# ProPrj__B__2024-11-06.net
KiCad netlist of a schematic drawn in EasyEDA Pro
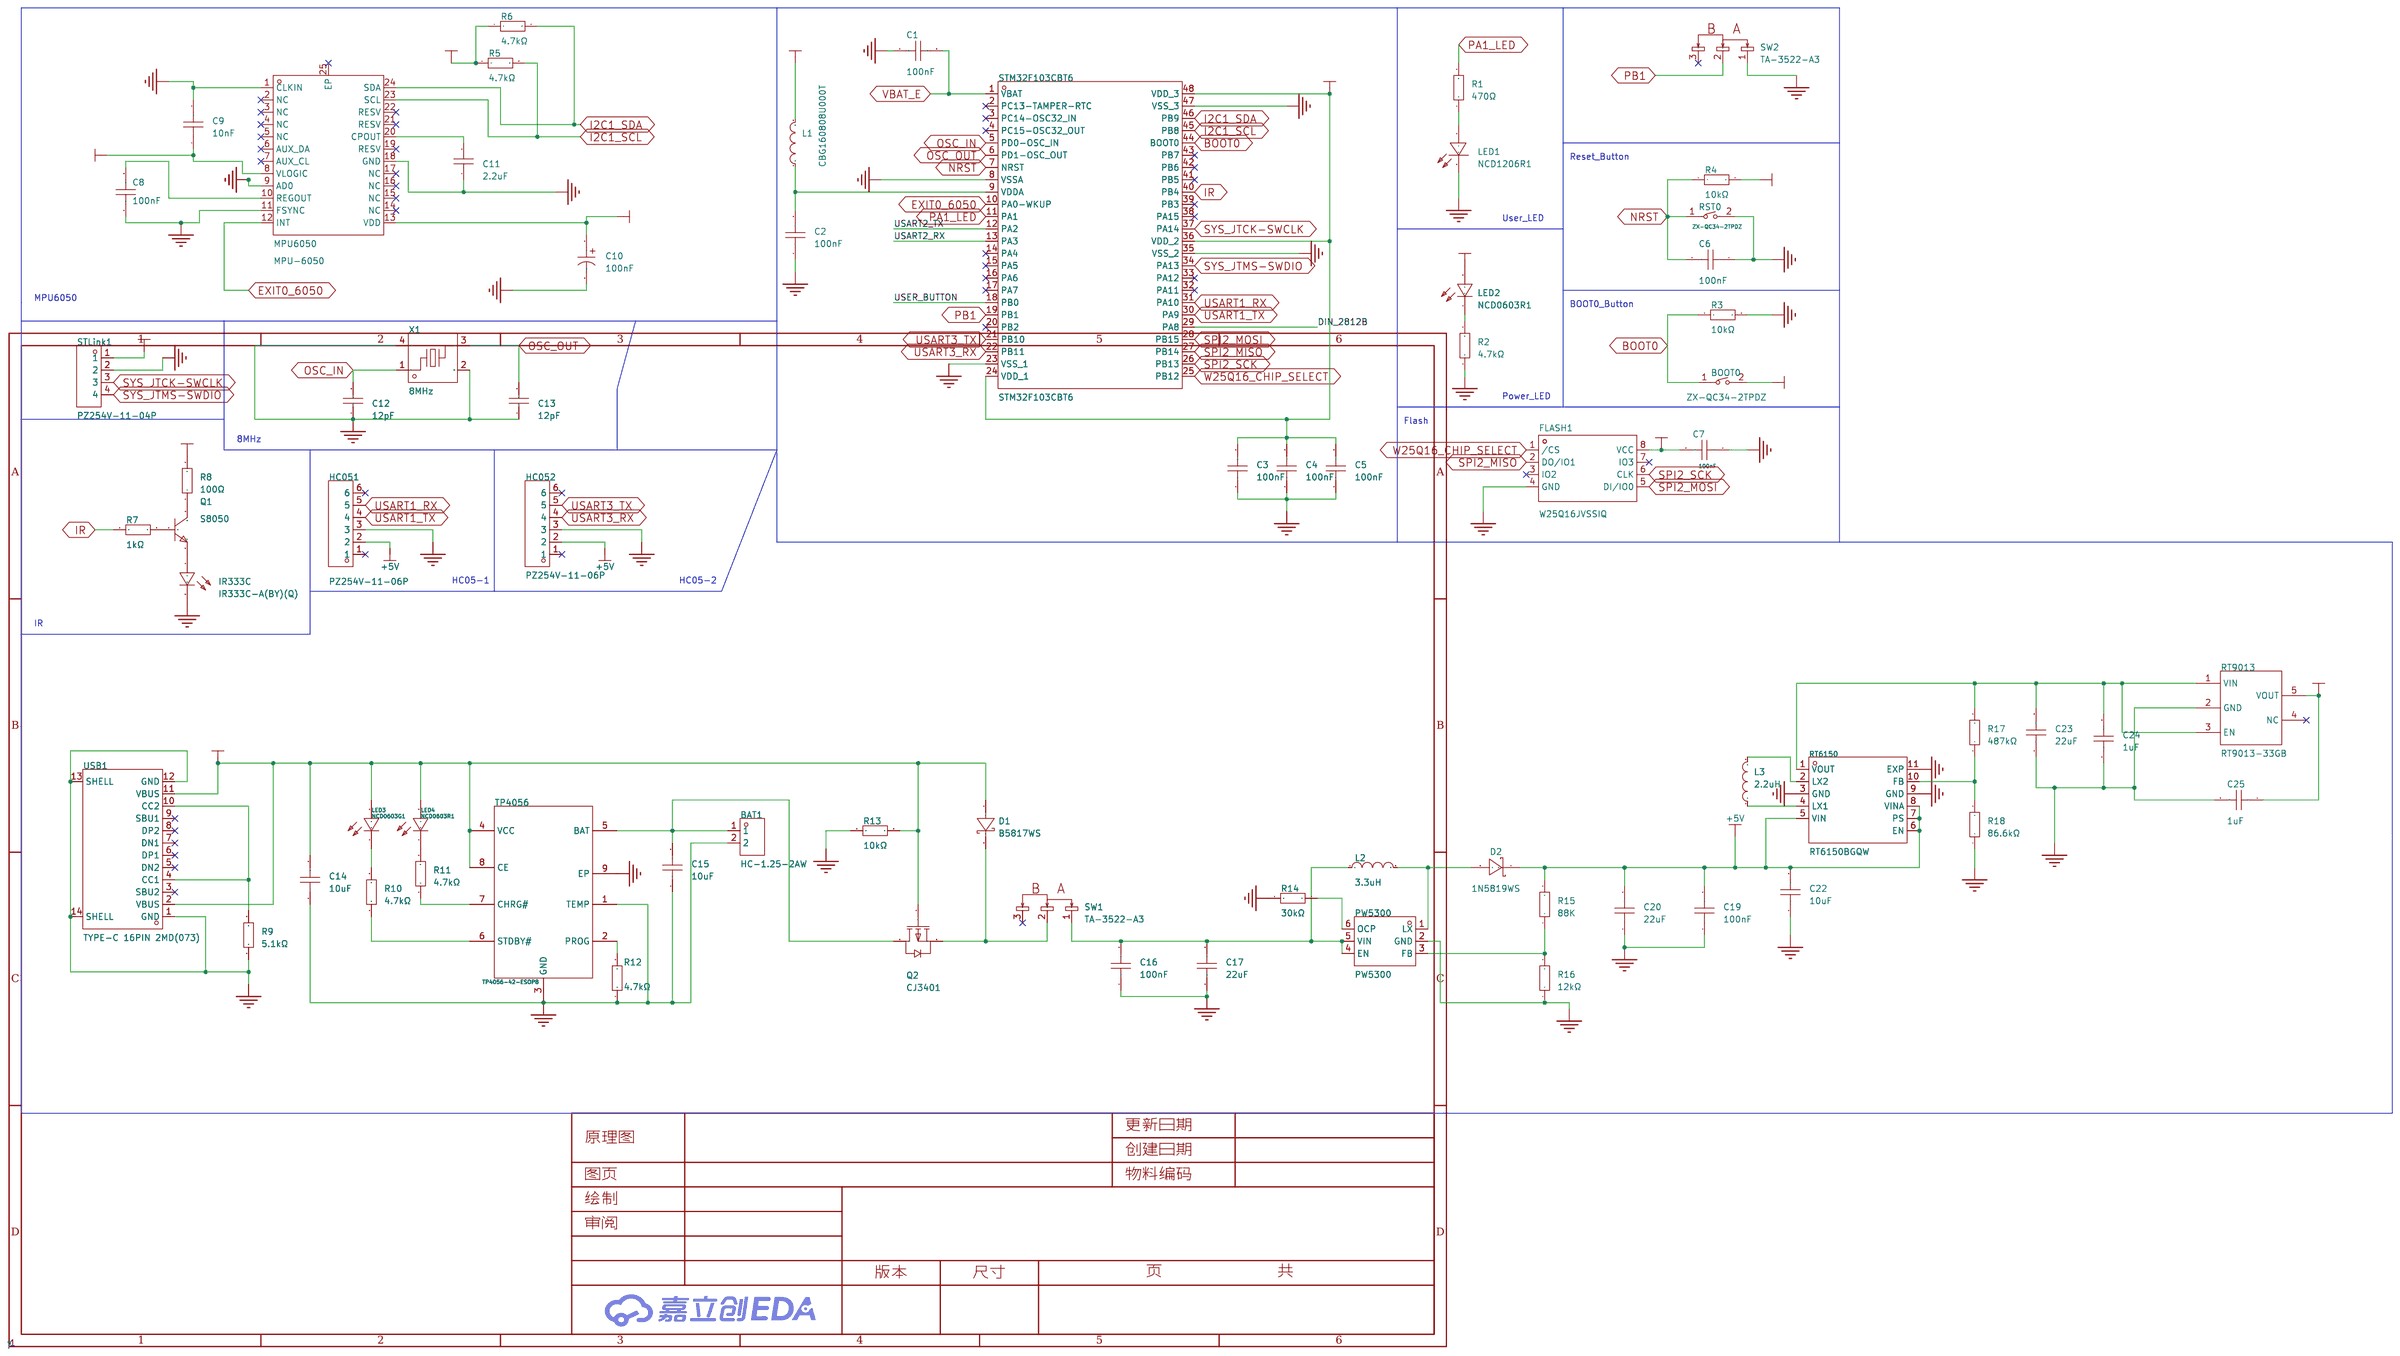
[diagram p0: schematic sheet]

(export (version "E")
  (design (tool "Eeschema 10.0.6"))
  (components
    (comp (ref "BAT1")
      (value "HC-1.25-2AW")
      (footprint "easyedapro:CONN-TH_2P-P1.25_HCTL_HC-1.25-2AW")
      (fields (field (name "Manufacturer") "HCTL(华灿天禄)"))
      (libsource (lib "easyedapro") (part "HC-1.25-2AW"))
    )
    (comp (ref "BOOT0")
      (value "ZX-QC34-2TPDZ")
      (footprint "easyedapro:KEY-SMD_L3.9-W3.0-LS5.0-EH")
      (fields (field (name "Manufacturer") "Megastar(兆星)"))
      (libsource (lib "easyedapro") (part "ZX-QC34-2TPDZ"))
    )
    (comp (ref "C1")
      (value "100nF")
      (footprint "easyedapro:C0603")
      (description "容值:100nF;精度:±10%;额定电压:50V;材质(温度系数):X7R;")
      (fields
        (field (name "Manufacturer Part") "CC0603KRX7R9BB104")
        (field (name "Manufacturer") "YAGEO(国巨)")
      )
      (libsource (lib "easyedapro") (part "CC0603KRX7R9BB104"))
    )
    (comp (ref "C2")
      (value "100nF")
      (footprint "easyedapro:C0603")
      (description "容值:100nF;精度:±10%;额定电压:50V;材质(温度系数):X7R;")
      (fields
        (field (name "Manufacturer Part") "CC0603KRX7R9BB104")
        (field (name "Manufacturer") "YAGEO(国巨)")
      )
      (libsource (lib "easyedapro") (part "CC0603KRX7R9BB104"))
    )
    (comp (ref "C3")
      (value "100nF")
      (footprint "easyedapro:C0603")
      (description "容值:100nF;精度:±10%;额定电压:50V;材质(温度系数):X7R;")
      (fields
        (field (name "Manufacturer Part") "CC0603KRX7R9BB104")
        (field (name "Manufacturer") "YAGEO(国巨)")
      )
      (libsource (lib "easyedapro") (part "CC0603KRX7R9BB104"))
    )
    (comp (ref "C4")
      (value "100nF")
      (footprint "easyedapro:C0603")
      (description "容值:100nF;精度:±10%;额定电压:50V;材质(温度系数):X7R;")
      (fields
        (field (name "Manufacturer Part") "CC0603KRX7R9BB104")
        (field (name "Manufacturer") "YAGEO(国巨)")
      )
      (libsource (lib "easyedapro") (part "CC0603KRX7R9BB104"))
    )
    (comp (ref "C5")
      (value "100nF")
      (footprint "easyedapro:C0603")
      (description "容值:100nF;精度:±10%;额定电压:50V;材质(温度系数):X7R;")
      (fields
        (field (name "Manufacturer Part") "CC0603KRX7R9BB104")
        (field (name "Manufacturer") "YAGEO(国巨)")
      )
      (libsource (lib "easyedapro") (part "CC0603KRX7R9BB104"))
    )
    (comp (ref "C6")
      (value "100nF")
      (footprint "easyedapro:C0603")
      (description "容值:100nF;精度:±10%;额定电压:50V;材质(温度系数):X7R;")
      (fields
        (field (name "Manufacturer Part") "CC0603KRX7R9BB104")
        (field (name "Manufacturer") "YAGEO(国巨)")
      )
      (libsource (lib "easyedapro") (part "CC0603KRX7R9BB104"))
    )
    (comp (ref "C7")
      (value "100nF")
      (footprint "easyedapro:C0603")
      (description "容值:100nF;精度:±10%;额定电压:50V;材质(温度系数):X7R;")
      (fields
        (field (name "Manufacturer Part") "CC0603KRX7R9BB104")
        (field (name "Manufacturer") "YAGEO(国巨)")
      )
      (libsource (lib "easyedapro") (part "CC0603KRX7R9BB104"))
    )
    (comp (ref "C8")
      (value "100nF")
      (footprint "easyedapro:C0603")
      (description "容值:100nF;精度:±10%;额定电压:50V;材质(温度系数):X7R;")
      (fields
        (field (name "Manufacturer Part") "CC0603KRX7R9BB104")
        (field (name "Manufacturer") "YAGEO(国巨)")
      )
      (libsource (lib "easyedapro") (part "CC0603KRX7R9BB104"))
    )
    (comp (ref "C9")
      (value "10nF")
      (footprint "easyedapro:C0603")
      (description "容值:100nF;精度:±10%;额定电压:50V;材质(温度系数):X7R;")
      (fields
        (field (name "Manufacturer Part") "CC0603KRX7R9BB103")
        (field (name "Manufacturer") "YAGEO(国巨)")
      )
      (libsource (lib "easyedapro") (part "CC0603KRX7R9BB104"))
    )
    (comp (ref "C10")
      (value "100nF")
      (footprint "easyedapro:CAP-SMD_L3.2-W1.6-FD")
      (description "容值:100nF;精度:±20%;额定电压:50V;等效串联电阻:20Ω;")
      (fields
        (field (name "Manufacturer Part") "CA45-A-35V-0.1UF-K")
        (field (name "Manufacturer") "CEC(振华新云)")
      )
      (libsource (lib "easyedapro") (part "T491A104M050AT"))
    )
    (comp (ref "C11")
      (value "2.2uF")
      (footprint "easyedapro:C0603")
      (description "容值:2.2uF;精度:±10%;额定电压:16V;材质(温度系数):X5R;")
      (fields
        (field (name "Manufacturer Part") "CL10A225KO8NNNC")
        (field (name "Manufacturer") "SAMSUNG(三星)")
      )
      (libsource (lib "easyedapro") (part "CL10A225KO8NNNC"))
    )
    (comp (ref "C12")
      (value "12pF")
      (footprint "easyedapro:C0603")
      (description "容值:12pF;精度:±5%;额定电压:50V;材质(温度系数):C0G;")
      (fields
        (field (name "Manufacturer Part") "CL10C120JB8NNNC")
        (field (name "Manufacturer") "SAMSUNG(三星)")
      )
      (libsource (lib "easyedapro") (part "CL10C120JB8NNNC"))
    )
    (comp (ref "C13")
      (value "12pF")
      (footprint "easyedapro:C0603")
      (description "容值:12pF;精度:±5%;额定电压:50V;材质(温度系数):C0G;")
      (fields
        (field (name "Manufacturer Part") "CL10C120JB8NNNC")
        (field (name "Manufacturer") "SAMSUNG(三星)")
      )
      (libsource (lib "easyedapro") (part "CL10C120JB8NNNC"))
    )
    (comp (ref "C14")
      (value "10uF")
      (footprint "easyedapro:C0603")
      (description "容值:10uF;精度:±20%;额定电压:16V;材质(温度系数):X5R;")
      (fields
        (field (name "Manufacturer Part") "HGC0603R5106M160NTHJ")
        (field (name "Manufacturer") "Chinocera(华瓷)")
      )
      (libsource (lib "easyedapro") (part "HGC0603R5106M160NTHJ"))
    )
    (comp (ref "C15")
      (value "10uF")
      (footprint "easyedapro:C0603")
      (description "容值:10uF;精度:±20%;额定电压:16V;材质(温度系数):X5R;")
      (fields
        (field (name "Manufacturer Part") "HGC0603R5106M160NTHJ")
        (field (name "Manufacturer") "Chinocera(华瓷)")
      )
      (libsource (lib "easyedapro") (part "HGC0603R5106M160NTHJ"))
    )
    (comp (ref "C16")
      (value "100nF")
      (footprint "easyedapro:C0603")
      (description "容值:100nF;精度:±10%;额定电压:50V;材质(温度系数):X7R;")
      (fields
        (field (name "Manufacturer Part") "CGA0603X7R104K500JT")
        (field (name "Manufacturer") "HRE(芯声)")
      )
      (libsource (lib "easyedapro") (part "cga0603x7r104k500jt"))
    )
    (comp (ref "C17")
      (value "22uF")
      (footprint "easyedapro:C0805")
      (description "容值:22uF;精度:±20%;额定电压:35V;材质(温度系数):X5R;")
      (fields
        (field (name "Manufacturer Part") "CGA0603X5R226M160JT")
        (field (name "Manufacturer") "HRE(芯声)")
      )
      (libsource (lib "easyedapro") (part "CGA0805X5R226M350MT"))
    )
    (comp (ref "C19")
      (value "100nF")
      (footprint "easyedapro:C0603")
      (description "容值:100nF;精度:±10%;额定电压:50V;材质(温度系数):X7R;")
      (fields
        (field (name "Manufacturer Part") "CGA0603X7R104K500JT")
        (field (name "Manufacturer") "HRE(芯声)")
      )
      (libsource (lib "easyedapro") (part "cga0603x7r104k500jt"))
    )
    (comp (ref "C20")
      (value "22uF")
      (footprint "easyedapro:C0805")
      (description "容值:22uF;精度:±20%;额定电压:35V;材质(温度系数):X5R;")
      (fields
        (field (name "Manufacturer Part") "CGA0603X5R226M160JT")
        (field (name "Manufacturer") "HRE(芯声)")
      )
      (libsource (lib "easyedapro") (part "CGA0805X5R226M350MT"))
    )
    (comp (ref "C22")
      (value "10uF")
      (footprint "easyedapro:C0603")
      (description "容值:10uF;精度:±20%;额定电压:16V;材质(温度系数):X5R;")
      (fields
        (field (name "Manufacturer Part") "HGC0603R5106M160NTHJ")
        (field (name "Manufacturer") "Chinocera(华瓷)")
      )
      (libsource (lib "easyedapro") (part "HGC0603R5106M160NTHJ"))
    )
    (comp (ref "C23")
      (value "22uF")
      (footprint "easyedapro:C0603")
      (description "容值:22uF;精度:±20%;额定电压:16V;材质(温度系数):X5R;")
      (fields
        (field (name "Manufacturer Part") "CGA0603X5R226M160JT")
        (field (name "Manufacturer") "HRE(芯声)")
      )
      (libsource (lib "easyedapro") (part "CGA0603X5R226M160JT"))
    )
    (comp (ref "C24")
      (value "1uF")
      (footprint "easyedapro:C0603")
      (description "容值:1uF;精度:±10%;额定电压:16V;材质(温度系数):X5R;")
      (fields
        (field (name "Manufacturer Part") "CGA0603X5R105K160JT")
        (field (name "Manufacturer") "HRE(芯声)")
      )
      (libsource (lib "easyedapro") (part "CGA0603X5R105K160JT"))
    )
    (comp (ref "C25")
      (value "1uF")
      (footprint "easyedapro:C0603")
      (description "容值:1uF;精度:±10%;额定电压:16V;材质(温度系数):X5R;")
      (fields
        (field (name "Manufacturer Part") "CGA0603X5R105K160JT")
        (field (name "Manufacturer") "HRE(芯声)")
      )
      (libsource (lib "easyedapro") (part "CGA0603X5R105K160JT"))
    )
    (comp (ref "D1")
      (value "B5817WS")
      (footprint "easyedapro:SOD-323_L1.7-W1.3-LS2.5-FD")
      (description "二极管配置:独立式;正向压降(Vf):450mV@1.0A;直流反向耐压(Vr):20V;平均整流电流(Io):1A;")
      (fields (field (name "Manufacturer") "宏迦橙"))
      (libsource (lib "easyedapro") (part "B5817WS_C7420329"))
    )
    (comp (ref "D2")
      (value "1N5819WS")
      (footprint "easyedapro:SMB_L4.6-W3.6-LS5.3-RD")
      (description "正向压降(Vf):500mV@3A;直流反向耐压(Vr):40V;平均整流电流(Io):3A;")
      (fields (field (name "Manufacturer") "Hottech(合科泰)"))
      (libsource (lib "easyedapro") (part "SS34_C266556"))
    )
    (comp (ref "FLASH1")
      (value "W25Q16JVSSIQ")
      (footprint "easyedapro:SOIC-8_L5.3-W5.3-P1.27-LS8.0-BL")
      (description "（与C82317为同一颗物料，只是编带方式不一样。）3V 16Mbit Serial Flash Memory with dual/quad SPI")
      (fields (field (name "Manufacturer") "WINBOND(华邦)"))
      (libsource (lib "easyedapro") (part "W25Q16JVSSIQTR"))
    )
    (comp (ref "HC051")
      (value "PZ254V-11-06P")
      (footprint "easyedapro:HDR-TH_6P-P2.54-V-M")
      (fields (field (name "Manufacturer") "XFCN(兴飞)"))
      (libsource (lib "easyedapro") (part "PZ254V-11-06P"))
    )
    (comp (ref "HC052")
      (value "PZ254V-11-06P")
      (footprint "easyedapro:HDR-TH_6P-P2.54-V-M")
      (fields (field (name "Manufacturer") "XFCN(兴飞)"))
      (libsource (lib "easyedapro") (part "PZ254V-11-06P"))
    )
    (comp (ref "IR333C")
      (value "IR333C-A(BY)(Q)")
      (footprint "easyedapro:LED-TH_BD5.0-P2.54-FD")
      (description "波长:940nm;")
      (fields (field (name "Manufacturer") "EVERLIGHT(亿光)"))
      (libsource (lib "easyedapro") (part "ir333c-a(by)(q)"))
    )
    (comp (ref "L1")
      (value "CBG160808U000T")
      (footprint "easyedapro:L0603")
      (description "标称阻抗@测试频率:0Ω@100MHz;直流电阻(RDC):100mΩ;")
      (fields (field (name "Manufacturer") "FH(风华)"))
      (libsource (lib "easyedapro") (part "CBG160808U000T"))
    )
    (comp (ref "L2")
      (value "3.3uH")
      (footprint "easyedapro:IND-SMD_L5.4-W5.2_FXL0530")
      (description "电感值:4.7uH;精度:±20%;额定电流:4.5A;饱和电流(Isat):5A;类型:一体成型电感;")
      (fields (field (name "Manufacturer Part") "VLS252012CX-3R3M-1") (field (name "Manufacturer") "TDK"))
      (libsource (lib "easyedapro") (part "FXL0530-4R7-M"))
    )
    (comp (ref "L3")
      (value "2.2uH")
      (footprint "easyedapro:IND-SMD_L2.5-W2.0_MHCHL2520")
      (description "电感值:2.2uH;精度:±20%;额定电流:3A;饱和电流(Isat):3.8A;类型:一体成型电感;")
      (fields
        (field (name "Manufacturer Part") "FTC252012S2R2MBCA")
        (field (name "Manufacturer") "cjiang(长江微电)")
      )
      (libsource (lib "easyedapro") (part "FTC252012S2R2MBCA"))
    )
    (comp (ref "LED1")
      (value "NCD1206R1")
      (footprint "easyedapro:LED1206-R-RD_RED")
      (fields (field (name "Manufacturer") "国星光电"))
      (libsource (lib "easyedapro") (part "FC-3215HRK-620D"))
    )
    (comp (ref "LED2")
      (value "NCD0603R1")
      (footprint "easyedapro:LED0603-RD_RED")
      (fields (field (name "Manufacturer") "国星光电"))
      (libsource (lib "easyedapro") (part "FC-DA1608HRK-620D"))
    )
    (comp (ref "LED3")
      (value "NCD0603G1")
      (footprint "easyedapro:led0603-rd_1")
      (fields (field (name "Manufacturer") "国星光电"))
      (libsource (lib "easyedapro") (part "FC-D1608UGK-520D10"))
    )
    (comp (ref "LED4")
      (value "NCD0603R1")
      (footprint "easyedapro:led0603-rd_1")
      (fields (field (name "Manufacturer") "国星光电"))
      (libsource (lib "easyedapro") (part "FC-D1608UGK-520D10"))
    )
    (comp (ref "MPU6050")
      (value "MPU-6050")
      (footprint "easyedapro:QFN-24_L4.0-W4.0-P0.50-BL-EP2.7")
      (description "传感器类型:加速度计陀螺仪;")
      (fields (field (name "Manufacturer") "TDK InvenSense(应美盛)"))
      (libsource (lib "easyedapro") (part "MPU-6050_C24112"))
    )
    (comp (ref "PW5300")
      (value "PW5300")
      (footprint "easyedapro:SOT-23-6_L2.9-W1.6-P0.95-LS2.8-BL")
      (libsource (lib "easyedapro") (part "PW5300"))
    )
    (comp (ref "Q1")
      (value "S8050")
      (footprint "easyedapro:SOT-23-3_L2.9-W1.6-P1.90-LS2.8-BR")
      (description "晶体管类型:NPN;集电极电流(Ic):500mA;集射极击穿电压(Vceo):25V;功率(Pd):300mW;")
      (fields (field (name "Manufacturer") "Hottech(合科泰)"))
      (libsource (lib "easyedapro") (part "S8050_C181158"))
    )
    (comp (ref "Q2")
      (value "CJ3401")
      (footprint "easyedapro:SOT-23-3_L2.9-W1.6-P1.90-LS2.8-BR")
      (fields (field (name "Manufacturer") "CJ(江苏长电/长晶)"))
      (libsource (lib "easyedapro") (part "CJ3401"))
    )
    (comp (ref "R1")
      (value "470Ω")
      (footprint "easyedapro:R0603")
      (description "电阻类型:厚膜电阻;阻值:470Ω;精度:±1%;功率:100mW;最大工作电压:75V;温度系数:±100ppm/°C;")
      (fields
        (field (name "Manufacturer Part") "0603WAF4700T5E")
        (field (name "Manufacturer") "UNI-ROYAL(厚声)")
      )
      (libsource (lib "easyedapro") (part "0603WAF4700T5E"))
    )
    (comp (ref "R2")
      (value "4.7kΩ")
      (footprint "easyedapro:R0603")
      (description "电阻类型:厚膜电阻;阻值:4.7kΩ;精度:±1%;功率:100mW;最大工作电压:75V;温度系数:±100ppm/°C;")
      (fields
        (field (name "Manufacturer Part") "0603WAF4701T5E")
        (field (name "Manufacturer") "UNI-ROYAL(厚声)")
      )
      (libsource (lib "easyedapro") (part "0603WAF4701T5E"))
    )
    (comp (ref "R3")
      (value "10kΩ")
      (footprint "easyedapro:R0603")
      (description "电阻类型:厚膜电阻;阻值:10kΩ;精度:±1%;功率:100mW;最大工作电压:75V;温度系数:±100ppm/°C;")
      (fields
        (field (name "Manufacturer Part") "0603WAF1002T5E")
        (field (name "Manufacturer") "UNI-ROYAL(厚声)")
      )
      (libsource (lib "easyedapro") (part "0603WAF1002T5E"))
    )
    (comp (ref "R4")
      (value "10kΩ")
      (footprint "easyedapro:R0603")
      (description "电阻类型:厚膜电阻;阻值:10kΩ;精度:±1%;功率:100mW;最大工作电压:75V;温度系数:±100ppm/°C;")
      (fields
        (field (name "Manufacturer Part") "0603WAF1002T5E")
        (field (name "Manufacturer") "UNI-ROYAL(厚声)")
      )
      (libsource (lib "easyedapro") (part "0603WAF1002T5E"))
    )
    (comp (ref "R5")
      (value "4.7kΩ")
      (footprint "easyedapro:R0603")
      (description "电阻类型:厚膜电阻;阻值:4.7kΩ;精度:±1%;功率:100mW;最大工作电压:75V;温度系数:±100ppm/°C;")
      (fields
        (field (name "Manufacturer Part") "0603WAF4701T5E")
        (field (name "Manufacturer") "UNI-ROYAL(厚声)")
      )
      (libsource (lib "easyedapro") (part "0603WAF4701T5E"))
    )
    (comp (ref "R6")
      (value "4.7kΩ")
      (footprint "easyedapro:R0603")
      (description "电阻类型:厚膜电阻;阻值:4.7kΩ;精度:±1%;功率:100mW;最大工作电压:75V;温度系数:±100ppm/°C;")
      (fields
        (field (name "Manufacturer Part") "0603WAF4701T5E")
        (field (name "Manufacturer") "UNI-ROYAL(厚声)")
      )
      (libsource (lib "easyedapro") (part "0603WAF4701T5E"))
    )
    (comp (ref "R7")
      (value "1kΩ")
      (footprint "easyedapro:R0603")
      (description "电阻类型:厚膜电阻;阻值:1kΩ;精度:±1%;功率:100mW;最大工作电压:75V;温度系数:±100ppm/°C;")
      (fields
        (field (name "Manufacturer Part") "0603WAF1001T5E")
        (field (name "Manufacturer") "UNI-ROYAL(厚声)")
      )
      (libsource (lib "easyedapro") (part "0603WAF1001T5E"))
    )
    (comp (ref "R8")
      (value "100Ω")
      (footprint "easyedapro:R0603")
      (description "电阻类型:厚膜电阻;阻值:100Ω;精度:±1%;功率:100mW;最大工作电压:75V;温度系数:±200ppm/°C;")
      (fields
        (field (name "Manufacturer Part") "0603WAF1000T5E")
        (field (name "Manufacturer") "UNI-ROYAL(厚声)")
      )
      (libsource (lib "easyedapro") (part "0603WAF1000T5E"))
    )
    (comp (ref "R9")
      (value "5.1kΩ")
      (footprint "easyedapro:R0603")
      (description "电阻类型:厚膜电阻;阻值:5.1kΩ;精度:±1%;功率:100mW;最大工作电压:75V;温度系数:±100ppm/°C;")
      (fields
        (field (name "Manufacturer Part") "0603WAF5101T5E")
        (field (name "Manufacturer") "UNI-ROYAL(厚声)")
      )
      (libsource (lib "easyedapro") (part "0603WAF5101T5E"))
    )
    (comp (ref "R10")
      (value "4.7kΩ")
      (footprint "easyedapro:R0603")
      (description "电阻类型:厚膜电阻;阻值:4.7kΩ;精度:±1%;功率:100mW;最大工作电压:75V;温度系数:±100ppm/°C;")
      (fields
        (field (name "Manufacturer Part") "0603WAF4701T5E")
        (field (name "Manufacturer") "UNI-ROYAL(厚声)")
      )
      (libsource (lib "easyedapro") (part "0603WAF4701T5E"))
    )
    (comp (ref "R11")
      (value "4.7kΩ")
      (footprint "easyedapro:R0603")
      (description "电阻类型:厚膜电阻;阻值:4.7kΩ;精度:±1%;功率:100mW;最大工作电压:75V;温度系数:±100ppm/°C;")
      (fields
        (field (name "Manufacturer Part") "0603WAF4701T5E")
        (field (name "Manufacturer") "UNI-ROYAL(厚声)")
      )
      (libsource (lib "easyedapro") (part "0603WAF4701T5E"))
    )
    (comp (ref "R12")
      (value "4.7kΩ")
      (footprint "easyedapro:R0603")
      (description "电阻类型:厚膜电阻;阻值:4.7kΩ;精度:±1%;功率:100mW;最大工作电压:75V;温度系数:±100ppm/°C;")
      (fields
        (field (name "Manufacturer Part") "0603WAF4701T5E")
        (field (name "Manufacturer") "UNI-ROYAL(厚声)")
      )
      (libsource (lib "easyedapro") (part "0603WAF4701T5E"))
    )
    (comp (ref "R13")
      (value "10kΩ")
      (footprint "easyedapro:R0603")
      (description "电阻类型:厚膜电阻;阻值:10kΩ;精度:±1%;功率:100mW;最大工作电压:75V;温度系数:±100ppm/°C;")
      (fields
        (field (name "Manufacturer Part") "0603WAF1002T5E")
        (field (name "Manufacturer") "UNI-ROYAL(厚声)")
      )
      (libsource (lib "easyedapro") (part "0603WAF1002T5E"))
    )
    (comp (ref "R14")
      (value "30kΩ")
      (footprint "easyedapro:R0603")
      (description "电阻类型:厚膜电阻;阻值:30kΩ;精度:±1%;功率:100mW;最大工作电压:75V;温度系数:±100ppm/°C;")
      (fields
        (field (name "Manufacturer Part") "0603WAF3002T5E")
        (field (name "Manufacturer") "UNI-ROYAL(厚声)")
      )
      (libsource (lib "easyedapro") (part "0603WAF3002T5E"))
    )
    (comp (ref "R15")
      (value "88K")
      (footprint "easyedapro:R0603")
      (fields
        (field (name "Manufacturer Part") "RCT0388K7FLF")
        (field (name "Manufacturer") "HKR(香港电阻)")
        (field (name "Tolerance") "±1%")
      )
      (libsource (lib "easyedapro") (part "电阻"))
    )
    (comp (ref "R16")
      (value "12kΩ")
      (footprint "easyedapro:R0603")
      (description "电阻类型:厚膜电阻;阻值:12kΩ;精度:±1%;功率:100mW;最大工作电压:75V;温度系数:±100ppm/°C;")
      (fields
        (field (name "Manufacturer Part") "0603WAF1202T5E")
        (field (name "Manufacturer") "UNI-ROYAL(厚声)")
      )
      (libsource (lib "easyedapro") (part "0603WAF1202T5E"))
    )
    (comp (ref "R17")
      (value "487kΩ")
      (footprint "easyedapro:R0603")
      (description "电阻类型:厚膜电阻;阻值:487kΩ;精度:±1%;功率:100mW;最大工作电压:75V;温度系数:±100ppm/°C;")
      (fields
        (field (name "Manufacturer Part") "0603WAF4873T5E")
        (field (name "Manufacturer") "UNI-ROYAL(厚声)")
      )
      (libsource (lib "easyedapro") (part "0603WAF4873T5E"))
    )
    (comp (ref "R18")
      (value "86.6kΩ")
      (footprint "easyedapro:R0603")
      (description "电阻类型:厚膜电阻;阻值:86.6kΩ;精度:±1%;功率:100mW;最大工作电压:75V;温度系数:±100ppm/°C;")
      (fields
        (field (name "Manufacturer Part") "0603WAF8662T5E")
        (field (name "Manufacturer") "UNI-ROYAL(厚声)")
      )
      (libsource (lib "easyedapro") (part "0603WAF8662T5E"))
    )
    (comp (ref "RST0")
      (value "ZX-QC34-2TPDZ")
      (footprint "easyedapro:KEY-SMD_L3.9-W3.0-LS5.0-EH")
      (fields (field (name "Manufacturer") "Megastar(兆星)"))
      (libsource (lib "easyedapro") (part "ZX-QC34-2TPDZ"))
    )
    (comp (ref "RT6150")
      (value "RT6150BGQW")
      (footprint "easyedapro:WSON-10_L2.5-W2.5-P0.50-BL-EP")
      (description "功能类型:升降压型;输入电压:1.8V~5.5V;输出电压:1.8V~5.5V;输出电流(最大值):800mA;")
      (fields (field (name "Manufacturer") "RICHTEK(立锜)"))
      (libsource (lib "easyedapro") (part "RT6150BGQW"))
    )
    (comp (ref "RT9013")
      (value "RT9013-33GB")
      (footprint "easyedapro:SOT-23-5_L3.0-W1.7-P0.95-LS2.8-BL")
      (description "输出类型:固定;最大输入电压:5.5V;输出电压:3.3V;最大输出电流:500mA;电源纹波抑制比(PSRR):50dB@(10kHz);输出极性:正极;")
      (fields (field (name "Manufacturer") "RICHTEK(立锜)"))
      (libsource (lib "easyedapro") (part "RT9013-33GB"))
    )
    (comp (ref "STLink1")
      (value "PZ254V-11-04P")
      (footprint "easyedapro:HDR-TH_4P-P2.54-V-M")
      (fields (field (name "Manufacturer") "XFCN(兴飞)"))
      (libsource (lib "easyedapro") (part "PZ254V-11-04P_C2691448"))
    )
    (comp (ref "STM32F103CBT6")
      (value "STM32F103CBT6")
      (fields (field (name "Manufacturer") "ST(意法半导体)"))
      (libsource (lib "easyedapro") (part "APM32F103CBT6"))
    )
    (comp (ref "SW1")
      (value "TA-3522-A3")
      (footprint "easyedapro:SW-TH_3P-L9.1-W3.5-P2.50-A3")
      (fields (field (name "Manufacturer") "Yuandi(元迪)"))
      (libsource (lib "easyedapro") (part "TA-3522-A3"))
    )
    (comp (ref "SW2")
      (value "TA-3522-A3")
      (footprint "easyedapro:SW-TH_3P-L9.1-W3.5-P2.50-A3")
      (fields (field (name "Manufacturer") "Yuandi(元迪)"))
      (libsource (lib "easyedapro") (part "TA-3522-A3"))
    )
    (comp (ref "TP4056")
      (value "TP4056-42-ESOP8")
      (footprint "easyedapro:ESOP-8_L4.9-W3.9-P1.27-LS6.0-BL-EP")
      (description "锂电池充电芯片 42代表电池满电电压4.2V。")
      (fields (field (name "Manufacturer") "TOPPOWER(南京拓微)"))
      (libsource (lib "easyedapro") (part "TP4056"))
    )
    (comp (ref "USB1")
      (value "TYPE-C 16PIN 2MD(073)")
      (footprint "easyedapro:USB-C-SMD_TYPE-C-6PIN-2MD-073")
      (description "连接器类型:Type-C;标准:USB 3.1;公母:母;安装方式:卧贴;触点数量:16P;端口数量:1;额定电流 - 电源:5A;工作温度范围:-25°C~+85°C;")
      (fields (field (name "Manufacturer") "SHOU HAN(首韩)"))
      (libsource (lib "easyedapro") (part "TYPE-C 16PIN 2MD(073)"))
    )
    (comp (ref "X1")
      (value "8MHz")
      (footprint "easyedapro:OSC-SMD_4P-L3.2-W2.5-BL")
      (description "晶振类型:贴片晶振;频率:8MHz;常温频差:±10ppm;外接负载电容:12pF;频率稳定度(全温):±20ppm;")
      (fields (field (name "Manufacturer Part") "X32258MOB4SI") (field (name "Manufacturer") "YXC(扬兴晶振)"))
      (libsource (lib "easyedapro") (part "x32258mob4si"))
    )
  )
  (nets
    (net (code "1") (name "+5V") (class "Default")
      (node (ref "C19") (pin "2") (pinfunction "2_2") (pintype "unspecified"))
      (node (ref "C20") (pin "2") (pinfunction "2_2") (pintype "unspecified"))
      (node (ref "C22") (pin "2") (pinfunction "2_2") (pintype "unspecified"))
      (node (ref "D2") (pin "1") (pinfunction "C_1") (pintype "unspecified"))
      (node (ref "HC051") (pin "2") (pinfunction "2_2") (pintype "unspecified"))
      (node (ref "HC052") (pin "2") (pinfunction "2_2") (pintype "unspecified"))
      (node (ref "R15") (pin "2") (pinfunction "2_2") (pintype "input"))
      (node (ref "RT6150") (pin "5") (pinfunction "VIN_5") (pintype "input"))
      (node (ref "RT6150") (pin "6") (pinfunction "EN_6") (pintype "input"))
      (node (ref "RT6150") (pin "7") (pinfunction "PS_7") (pintype "input"))
      (node (ref "RT6150") (pin "8") (pinfunction "VINA_8") (pintype "input"))
    )
    (net (code "2") (name "/DIN_2812B") (class "Default")
      (node (ref "STM32F103CBT6") (pin "29") (pinfunction "PA8_29") (pintype "unspecified"))
    )
    (net (code "3") (name "/USART2_RX") (class "Default")
      (node (ref "STM32F103CBT6") (pin "13") (pinfunction "PA3_13") (pintype "unspecified"))
    )
    (net (code "4") (name "/USART2_TX") (class "Default")
      (node (ref "STM32F103CBT6") (pin "12") (pinfunction "PA2_12") (pintype "unspecified"))
    )
    (net (code "5") (name "/USER_BUTTON") (class "Default")
      (node (ref "STM32F103CBT6") (pin "18") (pinfunction "PB0_18") (pintype "unspecified"))
    )
    (net (code "6") (name "3V3") (class "Default")
      (node (ref "BOOT0") (pin "2") (pinfunction "2_2") (pintype "unspecified"))
      (node (ref "C10") (pin "1") (pinfunction "1_1") (pintype "input"))
      (node (ref "C25") (pin "1") (pinfunction "1_1") (pintype "unspecified"))
      (node (ref "C3") (pin "2") (pinfunction "2_2") (pintype "unspecified"))
      (node (ref "C4") (pin "2") (pinfunction "2_2") (pintype "unspecified"))
      (node (ref "C5") (pin "2") (pinfunction "2_2") (pintype "unspecified"))
      (node (ref "C7") (pin "2") (pinfunction "2_2") (pintype "unspecified"))
      (node (ref "C9") (pin "1") (pinfunction "1_1") (pintype "unspecified"))
      (node (ref "FLASH1") (pin "8") (pinfunction "VCC_8") (pintype "unspecified"))
      (node (ref "L1") (pin "2") (pinfunction "2_2") (pintype "unspecified"))
      (node (ref "LED2") (pin "2") (pinfunction "A_2") (pintype "input"))
      (node (ref "MPU6050") (pin "13") (pinfunction "VDD_13") (pintype "unspecified"))
      (node (ref "MPU6050") (pin "8") (pinfunction "VLOGIC_8") (pintype "unspecified"))
      (node (ref "R4") (pin "2") (pinfunction "2_2") (pintype "input"))
      (node (ref "R5") (pin "1") (pinfunction "1_1") (pintype "input"))
      (node (ref "R6") (pin "1") (pinfunction "1_1") (pintype "input"))
      (node (ref "R8") (pin "2") (pinfunction "2_2") (pintype "input"))
      (node (ref "RT9013") (pin "5") (pinfunction "VOUT_5") (pintype "unspecified"))
      (node (ref "STLink1") (pin "1") (pinfunction "1_1") (pintype "unspecified"))
      (node (ref "STM32F103CBT6") (pin "24") (pinfunction "VDD_1_24") (pintype "unspecified"))
      (node (ref "STM32F103CBT6") (pin "36") (pinfunction "VDD_2_36") (pintype "unspecified"))
      (node (ref "STM32F103CBT6") (pin "48") (pinfunction "VDD_3_48") (pintype "unspecified"))
    )
    (net (code "7") (name "BOOT0") (class "Default")
      (node (ref "BOOT0") (pin "1") (pinfunction "1_1") (pintype "unspecified"))
      (node (ref "R3") (pin "1") (pinfunction "1_1") (pintype "input"))
      (node (ref "STM32F103CBT6") (pin "44") (pinfunction "BOOT0_44") (pintype "unspecified"))
    )
    (net (code "8") (name "EXIT0_6050") (class "Default")
      (node (ref "MPU6050") (pin "12") (pinfunction "INT_12") (pintype "unspecified"))
      (node (ref "STM32F103CBT6") (pin "10") (pinfunction "PA0-WKUP_10") (pintype "unspecified"))
    )
    (net (code "9") (name "GND") (class "Default")
      (node (ref "BAT1") (pin "2") (pinfunction "2_2") (pintype "unspecified"))
      (node (ref "C1") (pin "1") (pinfunction "1_1") (pintype "unspecified"))
      (node (ref "C10") (pin "2") (pinfunction "2_2") (pintype "input"))
      (node (ref "C11") (pin "1") (pinfunction "1_1") (pintype "input"))
      (node (ref "C12") (pin "1") (pinfunction "1_1") (pintype "input"))
      (node (ref "C13") (pin "1") (pinfunction "1_1") (pintype "input"))
      (node (ref "C14") (pin "1") (pinfunction "1_1") (pintype "unspecified"))
      (node (ref "C15") (pin "1") (pinfunction "1_1") (pintype "unspecified"))
      (node (ref "C16") (pin "1") (pinfunction "1_1") (pintype "unspecified"))
      (node (ref "C17") (pin "1") (pinfunction "1_1") (pintype "unspecified"))
      (node (ref "C19") (pin "1") (pinfunction "1_1") (pintype "unspecified"))
      (node (ref "C2") (pin "1") (pinfunction "1_1") (pintype "unspecified"))
      (node (ref "C20") (pin "1") (pinfunction "1_1") (pintype "unspecified"))
      (node (ref "C22") (pin "1") (pinfunction "1_1") (pintype "unspecified"))
      (node (ref "C23") (pin "1") (pinfunction "1_1") (pintype "unspecified"))
      (node (ref "C24") (pin "1") (pinfunction "1_1") (pintype "unspecified"))
      (node (ref "C25") (pin "2") (pinfunction "2_2") (pintype "unspecified"))
      (node (ref "C3") (pin "1") (pinfunction "1_1") (pintype "unspecified"))
      (node (ref "C4") (pin "1") (pinfunction "1_1") (pintype "unspecified"))
      (node (ref "C5") (pin "1") (pinfunction "1_1") (pintype "unspecified"))
      (node (ref "C6") (pin "1") (pinfunction "1_1") (pintype "unspecified"))
      (node (ref "C7") (pin "1") (pinfunction "1_1") (pintype "unspecified"))
      (node (ref "C8") (pin "1") (pinfunction "1_1") (pintype "unspecified"))
      (node (ref "C9") (pin "2") (pinfunction "2_2") (pintype "unspecified"))
      (node (ref "FLASH1") (pin "4") (pinfunction "GND_4") (pintype "unspecified"))
      (node (ref "HC051") (pin "3") (pinfunction "3_3") (pintype "unspecified"))
      (node (ref "HC052") (pin "3") (pinfunction "3_3") (pintype "unspecified"))
      (node (ref "IR333C") (pin "2") (pinfunction "C_2") (pintype "input"))
      (node (ref "LED1") (pin "2") (pinfunction "K_2") (pintype "unspecified"))
      (node (ref "MPU6050") (pin "1") (pinfunction "CLKIN_1") (pintype "unspecified"))
      (node (ref "MPU6050") (pin "11") (pinfunction "FSYNC_11") (pintype "unspecified"))
      (node (ref "MPU6050") (pin "18") (pinfunction "GND_18") (pintype "unspecified"))
      (node (ref "MPU6050") (pin "9") (pinfunction "AD0_9") (pintype "unspecified"))
      (node (ref "PW5300") (pin "2") (pinfunction "GND_2") (pintype "unspecified"))
      (node (ref "R12") (pin "1") (pinfunction "1_1") (pintype "input"))
      (node (ref "R13") (pin "1") (pinfunction "1_1") (pintype "input"))
      (node (ref "R14") (pin "1") (pinfunction "1_1") (pintype "input"))
      (node (ref "R16") (pin "1") (pinfunction "1_1") (pintype "input"))
      (node (ref "R18") (pin "1") (pinfunction "1_1") (pintype "input"))
      (node (ref "R2") (pin "1") (pinfunction "1_1") (pintype "input"))
      (node (ref "R3") (pin "2") (pinfunction "2_2") (pintype "input"))
      (node (ref "R9") (pin "1") (pinfunction "1_1") (pintype "input"))
      (node (ref "RST0") (pin "2") (pinfunction "2_2") (pintype "unspecified"))
      (node (ref "RT6150") (pin "11") (pinfunction "EXP_11") (pintype "input"))
      (node (ref "RT6150") (pin "3") (pinfunction "GND_3") (pintype "input"))
      (node (ref "RT6150") (pin "9") (pinfunction "GND_9") (pintype "input"))
      (node (ref "RT9013") (pin "2") (pinfunction "GND_2") (pintype "unspecified"))
      (node (ref "STLink1") (pin "2") (pinfunction "2_2") (pintype "unspecified"))
      (node (ref "STM32F103CBT6") (pin "23") (pinfunction "VSS_1_23") (pintype "unspecified"))
      (node (ref "STM32F103CBT6") (pin "35") (pinfunction "VSS_2_35") (pintype "unspecified"))
      (node (ref "STM32F103CBT6") (pin "47") (pinfunction "VSS_3_47") (pintype "unspecified"))
      (node (ref "STM32F103CBT6") (pin "8") (pinfunction "VSSA_8") (pintype "unspecified"))
      (node (ref "SW2") (pin "1") (pinfunction "1_1") (pintype "unspecified"))
      (node (ref "TP4056") (pin "1") (pinfunction "TEMP_1") (pintype "unspecified"))
      (node (ref "TP4056") (pin "3") (pinfunction "GND_3") (pintype "unspecified"))
      (node (ref "TP4056") (pin "9") (pinfunction "EP_9") (pintype "unspecified"))
      (node (ref "USB1") (pin "1") (pinfunction "GND_1") (pintype "unspecified"))
      (node (ref "USB1") (pin "12") (pinfunction "GND_12") (pintype "unspecified"))
      (node (ref "USB1") (pin "13") (pinfunction "SHELL_13") (pintype "unspecified"))
      (node (ref "USB1") (pin "14") (pinfunction "SHELL_14") (pintype "unspecified"))
      (node (ref "X1") (pin "2") (pinfunction "GND_2") (pintype "input"))
      (node (ref "X1") (pin "4") (pinfunction "GND_4") (pintype "input"))
    )
    (net (code "10") (name "I2C1_SCL") (class "Default")
      (node (ref "MPU6050") (pin "23") (pinfunction "SCL_23") (pintype "unspecified"))
      (node (ref "R5") (pin "2") (pinfunction "2_2") (pintype "input"))
      (node (ref "STM32F103CBT6") (pin "45") (pinfunction "PB8_45") (pintype "unspecified"))
    )
    (net (code "11") (name "I2C1_SDA") (class "Default")
      (node (ref "MPU6050") (pin "24") (pinfunction "SDA_24") (pintype "unspecified"))
      (node (ref "R6") (pin "2") (pinfunction "2_2") (pintype "input"))
      (node (ref "STM32F103CBT6") (pin "46") (pinfunction "PB9_46") (pintype "unspecified"))
    )
    (net (code "12") (name "IR") (class "Default")
      (node (ref "R7") (pin "1") (pinfunction "1_1") (pintype "input"))
      (node (ref "STM32F103CBT6") (pin "40") (pinfunction "PB4_40") (pintype "unspecified"))
    )
    (net (code "13") (name "NRST") (class "Default")
      (node (ref "C6") (pin "2") (pinfunction "2_2") (pintype "unspecified"))
      (node (ref "R4") (pin "1") (pinfunction "1_1") (pintype "input"))
      (node (ref "RST0") (pin "1") (pinfunction "1_1") (pintype "unspecified"))
      (node (ref "STM32F103CBT6") (pin "7") (pinfunction "NRST_7") (pintype "unspecified"))
    )
    (net (code "14") (name "Net-(D1-K)") (class "Default")
      (node (ref "D1") (pin "2") (pinfunction "K_2") (pintype "unspecified"))
      (node (ref "Q2") (pin "2") (pinfunction "S_2") (pintype "unspecified"))
      (node (ref "SW1") (pin "2") (pinfunction "2_2") (pintype "unspecified"))
    )
    (net (code "15") (name "Net-(D2-A)") (class "Default")
      (node (ref "D2") (pin "2") (pinfunction "A_2") (pintype "unspecified"))
      (node (ref "L2") (pin "2") (pinfunction "2_2") (pintype "unspecified"))
      (node (ref "PW5300") (pin "1") (pinfunction "LX_1") (pintype "unspecified"))
    )
    (net (code "16") (name "Net-(IR333C-A)") (class "Default")
      (node (ref "IR333C") (pin "1") (pinfunction "A_1") (pintype "input"))
      (node (ref "Q1") (pin "2") (pinfunction "2_2") (pintype "input"))
    )
    (net (code "17") (name "Net-(LED1-A)") (class "Default")
      (node (ref "LED1") (pin "1") (pinfunction "A_1") (pintype "unspecified"))
      (node (ref "R1") (pin "1") (pinfunction "1_1") (pintype "input"))
    )
    (net (code "18") (name "Net-(LED2-K)") (class "Default")
      (node (ref "LED2") (pin "1") (pinfunction "K_1") (pintype "input"))
      (node (ref "R2") (pin "2") (pinfunction "2_2") (pintype "input"))
    )
    (net (code "19") (name "Net-(LED3-K)") (class "Default")
      (node (ref "LED3") (pin "1") (pinfunction "K_1") (pintype "input"))
      (node (ref "R10") (pin "2") (pinfunction "2_2") (pintype "input"))
    )
    (net (code "20") (name "Net-(LED4-K)") (class "Default")
      (node (ref "LED4") (pin "1") (pinfunction "K_1") (pintype "input"))
      (node (ref "R11") (pin "2") (pinfunction "2_2") (pintype "input"))
    )
    (net (code "21") (name "Net-(MPU6050-CPOUT)") (class "Default")
      (node (ref "C11") (pin "2") (pinfunction "2_2") (pintype "input"))
      (node (ref "MPU6050") (pin "20") (pinfunction "CPOUT_20") (pintype "unspecified"))
    )
    (net (code "22") (name "Net-(MPU6050-REGOUT)") (class "Default")
      (node (ref "C8") (pin "2") (pinfunction "2_2") (pintype "unspecified"))
      (node (ref "MPU6050") (pin "10") (pinfunction "REGOUT_10") (pintype "unspecified"))
    )
    (net (code "23") (name "Net-(PW5300-EN)") (class "Default")
      (node (ref "C16") (pin "2") (pinfunction "2_2") (pintype "unspecified"))
      (node (ref "C17") (pin "2") (pinfunction "2_2") (pintype "unspecified"))
      (node (ref "L2") (pin "1") (pinfunction "1_1") (pintype "unspecified"))
      (node (ref "PW5300") (pin "4") (pinfunction "EN_4") (pintype "unspecified"))
      (node (ref "PW5300") (pin "5") (pinfunction "VIN_5") (pintype "unspecified"))
      (node (ref "SW1") (pin "1") (pinfunction "1_1") (pintype "unspecified"))
    )
    (net (code "24") (name "Net-(PW5300-FB)") (class "Default")
      (node (ref "PW5300") (pin "3") (pinfunction "FB_3") (pintype "unspecified"))
      (node (ref "R15") (pin "1") (pinfunction "1_1") (pintype "input"))
      (node (ref "R16") (pin "2") (pinfunction "2_2") (pintype "input"))
    )
    (net (code "25") (name "Net-(PW5300-OCP)") (class "Default")
      (node (ref "PW5300") (pin "6") (pinfunction "OCP_6") (pintype "unspecified"))
      (node (ref "R14") (pin "2") (pinfunction "2_2") (pintype "input"))
    )
    (net (code "26") (name "Net-(Q1-Pad1)") (class "Default")
      (node (ref "Q1") (pin "1") (pinfunction "1_1") (pintype "input"))
      (node (ref "R7") (pin "2") (pinfunction "2_2") (pintype "input"))
    )
    (net (code "27") (name "Net-(Q1-Pad3)") (class "Default")
      (node (ref "Q1") (pin "3") (pinfunction "3_3") (pintype "input"))
      (node (ref "R8") (pin "1") (pinfunction "1_1") (pintype "input"))
    )
    (net (code "28") (name "Net-(Q2-D)") (class "Default")
      (node (ref "BAT1") (pin "1") (pinfunction "1_1") (pintype "unspecified"))
      (node (ref "C15") (pin "2") (pinfunction "2_2") (pintype "unspecified"))
      (node (ref "Q2") (pin "3") (pinfunction "D_3") (pintype "unspecified"))
      (node (ref "TP4056") (pin "5") (pinfunction "BAT_5") (pintype "unspecified"))
    )
    (net (code "29") (name "Net-(RT6150-FB)") (class "Default")
      (node (ref "R17") (pin "1") (pinfunction "1_1") (pintype "input"))
      (node (ref "R18") (pin "2") (pinfunction "2_2") (pintype "input"))
      (node (ref "RT6150") (pin "10") (pinfunction "FB_10") (pintype "input"))
    )
    (net (code "30") (name "Net-(RT6150-LX1)") (class "Default")
      (node (ref "L3") (pin "1") (pinfunction "1_1") (pintype "unspecified"))
      (node (ref "RT6150") (pin "4") (pinfunction "LX1_4") (pintype "input"))
    )
    (net (code "31") (name "Net-(RT6150-LX2)") (class "Default")
      (node (ref "L3") (pin "2") (pinfunction "2_2") (pintype "unspecified"))
      (node (ref "RT6150") (pin "2") (pinfunction "LX2_2") (pintype "input"))
    )
    (net (code "32") (name "Net-(RT6150-VOUT)") (class "Default")
      (node (ref "C23") (pin "2") (pinfunction "2_2") (pintype "unspecified"))
      (node (ref "C24") (pin "2") (pinfunction "2_2") (pintype "unspecified"))
      (node (ref "R17") (pin "2") (pinfunction "2_2") (pintype "input"))
      (node (ref "RT6150") (pin "1") (pinfunction "VOUT_1") (pintype "input"))
      (node (ref "RT9013") (pin "1") (pinfunction "VIN_1") (pintype "unspecified"))
      (node (ref "RT9013") (pin "3") (pinfunction "EN_3") (pintype "unspecified"))
    )
    (net (code "33") (name "Net-(STM32F103CBT6-VDDA)") (class "Default")
      (node (ref "C2") (pin "2") (pinfunction "2_2") (pintype "unspecified"))
      (node (ref "L1") (pin "1") (pinfunction "1_1") (pintype "unspecified"))
      (node (ref "STM32F103CBT6") (pin "9") (pinfunction "VDDA_9") (pintype "unspecified"))
    )
    (net (code "34") (name "Net-(TP4056-CHRG#)") (class "Default")
      (node (ref "R11") (pin "1") (pinfunction "1_1") (pintype "input"))
      (node (ref "TP4056") (pin "7") (pinfunction "CHRG#_7") (pintype "unspecified"))
    )
    (net (code "35") (name "Net-(TP4056-PROG)") (class "Default")
      (node (ref "R12") (pin "2") (pinfunction "2_2") (pintype "input"))
      (node (ref "TP4056") (pin "2") (pinfunction "PROG_2") (pintype "unspecified"))
    )
    (net (code "36") (name "Net-(TP4056-STDBY#)") (class "Default")
      (node (ref "R10") (pin "1") (pinfunction "1_1") (pintype "input"))
      (node (ref "TP4056") (pin "6") (pinfunction "STDBY#_6") (pintype "unspecified"))
    )
    (net (code "37") (name "Net-(USB1-CC1)") (class "Default")
      (node (ref "R9") (pin "2") (pinfunction "2_2") (pintype "input"))
      (node (ref "USB1") (pin "10") (pinfunction "CC2_10") (pintype "unspecified"))
      (node (ref "USB1") (pin "4") (pinfunction "CC1_4") (pintype "unspecified"))
    )
    (net (code "38") (name "OSC_IN") (class "Default")
      (node (ref "C12") (pin "2") (pinfunction "2_2") (pintype "input"))
      (node (ref "STM32F103CBT6") (pin "5") (pinfunction "PD0-OSC_IN_5") (pintype "unspecified"))
      (node (ref "X1") (pin "1") (pinfunction "1_1") (pintype "input"))
    )
    (net (code "39") (name "OSC_OUT") (class "Default")
      (node (ref "C13") (pin "2") (pinfunction "2_2") (pintype "input"))
      (node (ref "STM32F103CBT6") (pin "6") (pinfunction "PD1-OSC_OUT_6") (pintype "unspecified"))
      (node (ref "X1") (pin "3") (pinfunction "3_3") (pintype "input"))
    )
    (net (code "40") (name "PA1_LED") (class "Default")
      (node (ref "R1") (pin "2") (pinfunction "2_2") (pintype "input"))
      (node (ref "STM32F103CBT6") (pin "11") (pinfunction "PA1_11") (pintype "unspecified"))
    )
    (net (code "41") (name "PB1") (class "Default")
      (node (ref "STM32F103CBT6") (pin "19") (pinfunction "PB1_19") (pintype "unspecified"))
      (node (ref "SW2") (pin "2") (pinfunction "2_2") (pintype "unspecified"))
    )
    (net (code "42") (name "SPI2_MISO") (class "Default")
      (node (ref "FLASH1") (pin "2") (pinfunction "DO/IO1_2") (pintype "unspecified"))
      (node (ref "STM32F103CBT6") (pin "27") (pinfunction "PB14_27") (pintype "unspecified"))
    )
    (net (code "43") (name "SPI2_MOSI") (class "Default")
      (node (ref "FLASH1") (pin "5") (pinfunction "DI/IO0_5") (pintype "unspecified"))
      (node (ref "STM32F103CBT6") (pin "28") (pinfunction "PB15_28") (pintype "unspecified"))
    )
    (net (code "44") (name "SPI2_SCK") (class "Default")
      (node (ref "FLASH1") (pin "6") (pinfunction "CLK_6") (pintype "unspecified"))
      (node (ref "STM32F103CBT6") (pin "26") (pinfunction "PB13_26") (pintype "unspecified"))
    )
    (net (code "45") (name "SYS_JTCK-SWCLK") (class "Default")
      (node (ref "STLink1") (pin "3") (pinfunction "3_3") (pintype "unspecified"))
      (node (ref "STM32F103CBT6") (pin "37") (pinfunction "PA14_37") (pintype "unspecified"))
    )
    (net (code "46") (name "SYS_JTMS-SWDIO") (class "Default")
      (node (ref "STLink1") (pin "4") (pinfunction "4_4") (pintype "unspecified"))
      (node (ref "STM32F103CBT6") (pin "34") (pinfunction "PA13_34") (pintype "unspecified"))
    )
    (net (code "47") (name "USART1_RX") (class "Default")
      (node (ref "HC051") (pin "5") (pinfunction "5_5") (pintype "unspecified"))
      (node (ref "STM32F103CBT6") (pin "31") (pinfunction "PA10_31") (pintype "unspecified"))
    )
    (net (code "48") (name "USART1_TX") (class "Default")
      (node (ref "HC051") (pin "4") (pinfunction "4_4") (pintype "unspecified"))
      (node (ref "STM32F103CBT6") (pin "30") (pinfunction "PA9_30") (pintype "unspecified"))
    )
    (net (code "49") (name "USART3_RX") (class "Default")
      (node (ref "HC052") (pin "4") (pinfunction "4_4") (pintype "unspecified"))
      (node (ref "STM32F103CBT6") (pin "22") (pinfunction "PB11_22") (pintype "unspecified"))
    )
    (net (code "50") (name "USART3_TX") (class "Default")
      (node (ref "HC052") (pin "5") (pinfunction "5_5") (pintype "unspecified"))
      (node (ref "STM32F103CBT6") (pin "21") (pinfunction "PB10_21") (pintype "unspecified"))
    )
    (net (code "51") (name "VBAT_E") (class "Default")
      (node (ref "C1") (pin "2") (pinfunction "2_2") (pintype "unspecified"))
      (node (ref "STM32F103CBT6") (pin "1") (pinfunction "VBAT_1") (pintype "unspecified"))
    )
    (net (code "52") (name "VCC_USB") (class "Default")
      (node (ref "C14") (pin "2") (pinfunction "2_2") (pintype "unspecified"))
      (node (ref "D1") (pin "1") (pinfunction "A_1") (pintype "unspecified"))
      (node (ref "LED3") (pin "2") (pinfunction "A_2") (pintype "input"))
      (node (ref "LED4") (pin "2") (pinfunction "A_2") (pintype "input"))
      (node (ref "Q2") (pin "1") (pinfunction "G_1") (pintype "unspecified"))
      (node (ref "R13") (pin "2") (pinfunction "2_2") (pintype "input"))
      (node (ref "TP4056") (pin "4") (pinfunction "VCC_4") (pintype "unspecified"))
      (node (ref "TP4056") (pin "8") (pinfunction "CE_8") (pintype "unspecified"))
      (node (ref "USB1") (pin "11") (pinfunction "VBUS_11") (pintype "unspecified"))
      (node (ref "USB1") (pin "2") (pinfunction "VBUS_2") (pintype "unspecified"))
    )
    (net (code "53") (name "W25Q16_CHIP_SELECT") (class "Default")
      (node (ref "FLASH1") (pin "1") (pinfunction "/CS_1") (pintype "unspecified"))
      (node (ref "STM32F103CBT6") (pin "25") (pinfunction "PB12_25") (pintype "unspecified"))
    )
    (net (code "54") (name "unconnected-(FLASH1-IO2-Pad3)") (class "Default")
      (node (ref "FLASH1") (pin "3") (pinfunction "IO2_3") (pintype "unspecified+no_connect"))
    )
    (net (code "55") (name "unconnected-(FLASH1-IO3-Pad7)") (class "Default")
      (node (ref "FLASH1") (pin "7") (pinfunction "IO3_7") (pintype "unspecified+no_connect"))
    )
    (net (code "56") (name "unconnected-(HC051-Pad1)") (class "Default")
      (node (ref "HC051") (pin "1") (pinfunction "1_1") (pintype "unspecified+no_connect"))
    )
    (net (code "57") (name "unconnected-(HC051-Pad6)") (class "Default")
      (node (ref "HC051") (pin "6") (pinfunction "6_6") (pintype "unspecified+no_connect"))
    )
    (net (code "58") (name "unconnected-(HC052-Pad1)") (class "Default")
      (node (ref "HC052") (pin "1") (pinfunction "1_1") (pintype "unspecified+no_connect"))
    )
    (net (code "59") (name "unconnected-(HC052-Pad6)") (class "Default")
      (node (ref "HC052") (pin "6") (pinfunction "6_6") (pintype "unspecified+no_connect"))
    )
    (net (code "60") (name "unconnected-(MPU6050-AUX_CL-Pad7)") (class "Default")
      (node (ref "MPU6050") (pin "7") (pinfunction "AUX_CL_7") (pintype "unspecified+no_connect"))
    )
    (net (code "61") (name "unconnected-(MPU6050-AUX_DA-Pad6)") (class "Default")
      (node (ref "MPU6050") (pin "6") (pinfunction "AUX_DA_6") (pintype "unspecified+no_connect"))
    )
    (net (code "62") (name "unconnected-(MPU6050-EP-Pad25)") (class "Default")
      (node (ref "MPU6050") (pin "25") (pinfunction "EP_25") (pintype "unspecified+no_connect"))
    )
    (net (code "63") (name "unconnected-(MPU6050-NC-Pad2)") (class "Default")
      (node (ref "MPU6050") (pin "2") (pinfunction "NC_2") (pintype "unspecified+no_connect"))
    )
    (net (code "64") (name "unconnected-(MPU6050-NC-Pad3)") (class "Default")
      (node (ref "MPU6050") (pin "3") (pinfunction "NC_3") (pintype "unspecified+no_connect"))
    )
    (net (code "65") (name "unconnected-(MPU6050-NC-Pad4)") (class "Default")
      (node (ref "MPU6050") (pin "4") (pinfunction "NC_4") (pintype "unspecified+no_connect"))
    )
    (net (code "66") (name "unconnected-(MPU6050-NC-Pad5)") (class "Default")
      (node (ref "MPU6050") (pin "5") (pinfunction "NC_5") (pintype "unspecified+no_connect"))
    )
    (net (code "67") (name "unconnected-(MPU6050-NC-Pad14)") (class "Default")
      (node (ref "MPU6050") (pin "14") (pinfunction "NC_14") (pintype "unspecified+no_connect"))
    )
    (net (code "68") (name "unconnected-(MPU6050-NC-Pad15)") (class "Default")
      (node (ref "MPU6050") (pin "15") (pinfunction "NC_15") (pintype "unspecified+no_connect"))
    )
    (net (code "69") (name "unconnected-(MPU6050-NC-Pad16)") (class "Default")
      (node (ref "MPU6050") (pin "16") (pinfunction "NC_16") (pintype "unspecified+no_connect"))
    )
    (net (code "70") (name "unconnected-(MPU6050-NC-Pad17)") (class "Default")
      (node (ref "MPU6050") (pin "17") (pinfunction "NC_17") (pintype "unspecified+no_connect"))
    )
    (net (code "71") (name "unconnected-(MPU6050-RESV-Pad19)") (class "Default")
      (node (ref "MPU6050") (pin "19") (pinfunction "RESV_19") (pintype "unspecified+no_connect"))
    )
    (net (code "72") (name "unconnected-(MPU6050-RESV-Pad21)") (class "Default")
      (node (ref "MPU6050") (pin "21") (pinfunction "RESV_21") (pintype "unspecified+no_connect"))
    )
    (net (code "73") (name "unconnected-(MPU6050-RESV-Pad22)") (class "Default")
      (node (ref "MPU6050") (pin "22") (pinfunction "RESV_22") (pintype "unspecified+no_connect"))
    )
    (net (code "74") (name "unconnected-(RT9013-NC-Pad4)") (class "Default")
      (node (ref "RT9013") (pin "4") (pinfunction "NC_4") (pintype "unspecified+no_connect"))
    )
    (net (code "75") (name "unconnected-(STM32F103CBT6-PA4-Pad14)") (class "Default")
      (node (ref "STM32F103CBT6") (pin "14") (pinfunction "PA4_14") (pintype "unspecified+no_connect"))
    )
    (net (code "76") (name "unconnected-(STM32F103CBT6-PA5-Pad15)") (class "Default")
      (node (ref "STM32F103CBT6") (pin "15") (pinfunction "PA5_15") (pintype "unspecified+no_connect"))
    )
    (net (code "77") (name "unconnected-(STM32F103CBT6-PA6-Pad16)") (class "Default")
      (node (ref "STM32F103CBT6") (pin "16") (pinfunction "PA6_16") (pintype "unspecified+no_connect"))
    )
    (net (code "78") (name "unconnected-(STM32F103CBT6-PA7-Pad17)") (class "Default")
      (node (ref "STM32F103CBT6") (pin "17") (pinfunction "PA7_17") (pintype "unspecified+no_connect"))
    )
    (net (code "79") (name "unconnected-(STM32F103CBT6-PA11-Pad32)") (class "Default")
      (node (ref "STM32F103CBT6") (pin "32") (pinfunction "PA11_32") (pintype "unspecified+no_connect"))
    )
    (net (code "80") (name "unconnected-(STM32F103CBT6-PA12-Pad33)") (class "Default")
      (node (ref "STM32F103CBT6") (pin "33") (pinfunction "PA12_33") (pintype "unspecified+no_connect"))
    )
    (net (code "81") (name "unconnected-(STM32F103CBT6-PA15-Pad38)") (class "Default")
      (node (ref "STM32F103CBT6") (pin "38") (pinfunction "PA15_38") (pintype "unspecified+no_connect"))
    )
    (net (code "82") (name "unconnected-(STM32F103CBT6-PB2-Pad20)") (class "Default")
      (node (ref "STM32F103CBT6") (pin "20") (pinfunction "PB2_20") (pintype "unspecified+no_connect"))
    )
    (net (code "83") (name "unconnected-(STM32F103CBT6-PB3-Pad39)") (class "Default")
      (node (ref "STM32F103CBT6") (pin "39") (pinfunction "PB3_39") (pintype "unspecified+no_connect"))
    )
    (net (code "84") (name "unconnected-(STM32F103CBT6-PB5-Pad41)") (class "Default")
      (node (ref "STM32F103CBT6") (pin "41") (pinfunction "PB5_41") (pintype "unspecified+no_connect"))
    )
    (net (code "85") (name "unconnected-(STM32F103CBT6-PB6-Pad42)") (class "Default")
      (node (ref "STM32F103CBT6") (pin "42") (pinfunction "PB6_42") (pintype "unspecified+no_connect"))
    )
    (net (code "86") (name "unconnected-(STM32F103CBT6-PB7-Pad43)") (class "Default")
      (node (ref "STM32F103CBT6") (pin "43") (pinfunction "PB7_43") (pintype "unspecified+no_connect"))
    )
    (net (code "87") (name "unconnected-(STM32F103CBT6-PC13-TAMPER-RTC-Pad2)") (class "Default")
      (node (ref "STM32F103CBT6") (pin "2") (pinfunction "PC13-TAMPER-RTC_2") (pintype "unspecified+no_connect"))
    )
    (net (code "88") (name "unconnected-(STM32F103CBT6-PC14-OSC32_IN-Pad3)") (class "Default")
      (node (ref "STM32F103CBT6") (pin "3") (pinfunction "PC14-OSC32_IN_3") (pintype "unspecified+no_connect"))
    )
    (net (code "89") (name "unconnected-(STM32F103CBT6-PC15-OSC32_OUT-Pad4)") (class "Default")
      (node (ref "STM32F103CBT6") (pin "4") (pinfunction "PC15-OSC32_OUT_4") (pintype "unspecified+no_connect"))
    )
    (net (code "90") (name "unconnected-(SW1-Pad3)") (class "Default")
      (node (ref "SW1") (pin "3") (pinfunction "3_3") (pintype "unspecified+no_connect"))
    )
    (net (code "91") (name "unconnected-(SW2-Pad3)") (class "Default")
      (node (ref "SW2") (pin "3") (pinfunction "3_3") (pintype "unspecified+no_connect"))
    )
    (net (code "92") (name "unconnected-(USB1-DN1-Pad7)") (class "Default")
      (node (ref "USB1") (pin "7") (pinfunction "DN1_7") (pintype "unspecified+no_connect"))
    )
    (net (code "93") (name "unconnected-(USB1-DN2-Pad5)") (class "Default")
      (node (ref "USB1") (pin "5") (pinfunction "DN2_5") (pintype "unspecified+no_connect"))
    )
    (net (code "94") (name "unconnected-(USB1-DP1-Pad6)") (class "Default")
      (node (ref "USB1") (pin "6") (pinfunction "DP1_6") (pintype "unspecified+no_connect"))
    )
    (net (code "95") (name "unconnected-(USB1-DP2-Pad8)") (class "Default")
      (node (ref "USB1") (pin "8") (pinfunction "DP2_8") (pintype "unspecified+no_connect"))
    )
    (net (code "96") (name "unconnected-(USB1-SBU1-Pad9)") (class "Default")
      (node (ref "USB1") (pin "9") (pinfunction "SBU1_9") (pintype "unspecified+no_connect"))
    )
    (net (code "97") (name "unconnected-(USB1-SBU2-Pad3)") (class "Default")
      (node (ref "USB1") (pin "3") (pinfunction "SBU2_3") (pintype "unspecified+no_connect"))
    )
  )
)
